# 3_-_19V_Buck.net
KiCad netlist of a schematic drawn in Altium Designer
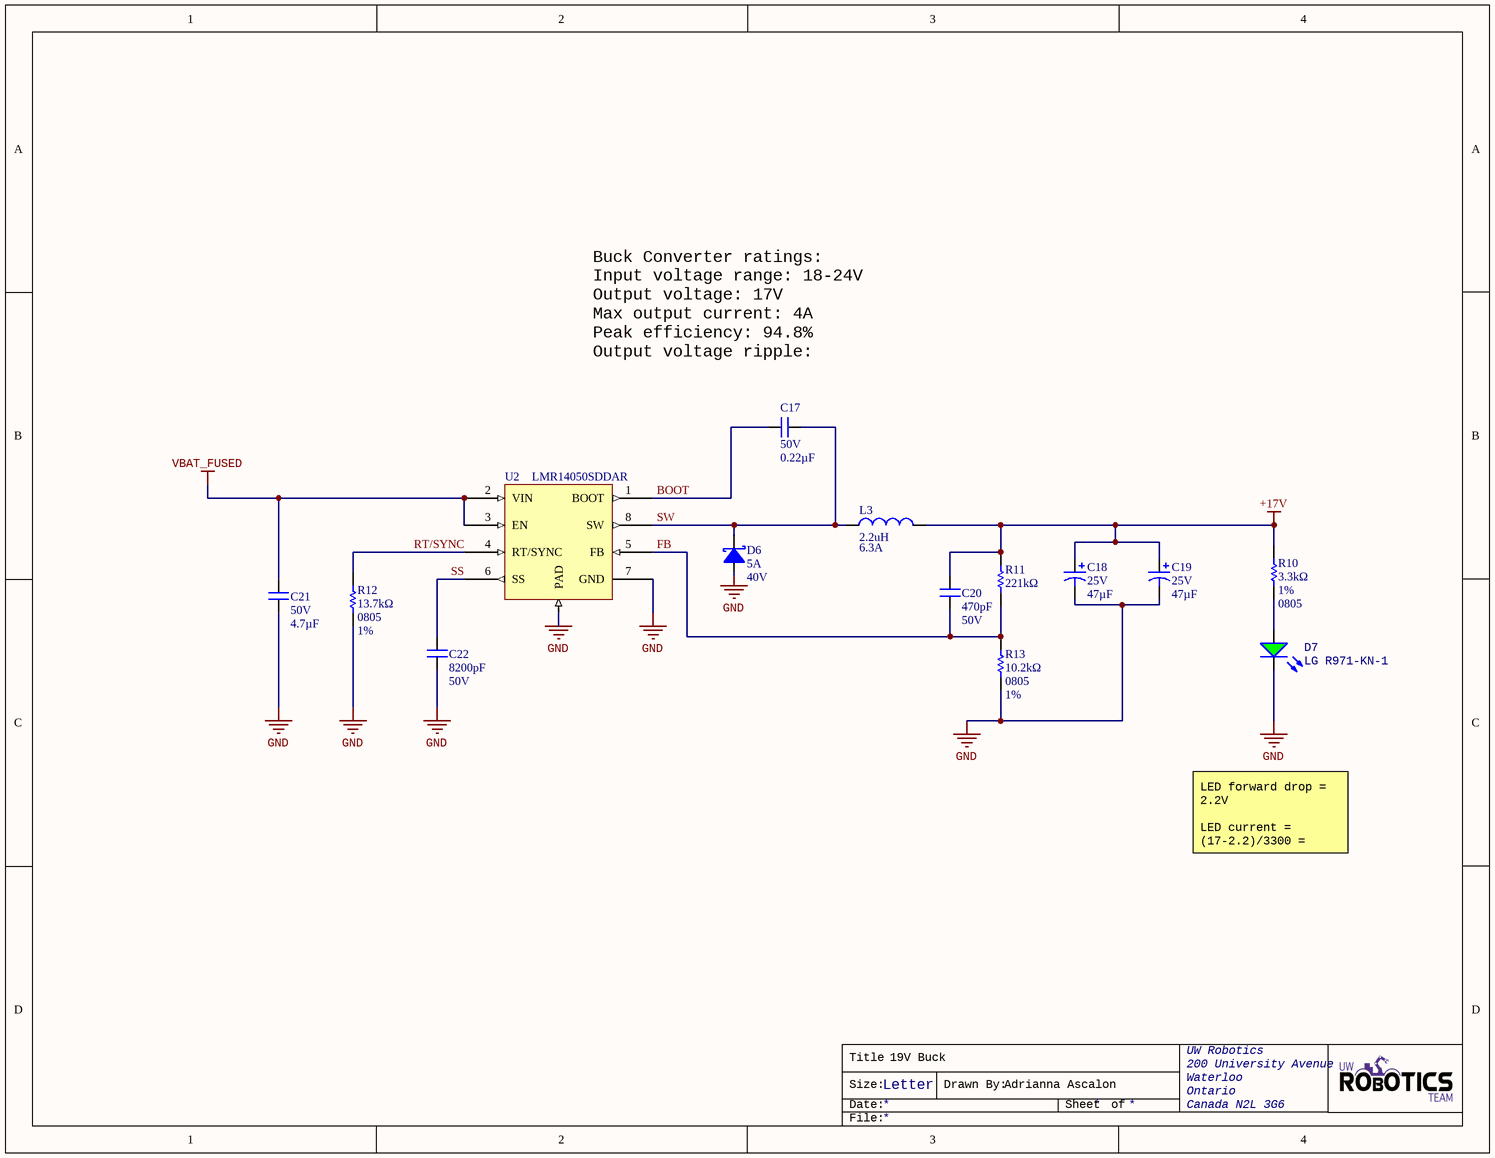
[diagram p0: 3 - 19V Buck.SchDoc]

(export (version "E")
  (design (tool "Eeschema 10.0.6"))
  (components
    (comp (ref "C17")
      (value "GRM21BR71H224MA01L")
      (footprint "CAP 0805_2012")
      (description "CAP CER 0.22UF 50V X7R 0805")
      (fields
        (field (name "TOLERANCE") "20%")
        (field (name "VOLTAGE RATING") "50V")
        (field (name "CAPACITANCE") "0.22µF")
      )
      (libsource (lib "UWRT_Schematic_Library_2020") (part "GRM21BR71H224MA01L"))
    )
    (comp (ref "C18")
      (value "47μF")
      (footprint "25SVPF47M")
      (description "CAP ALUM POLY 47UF 20% 25V SMD")
      (fields
        (field (name "TOLERANCE") "20%")
        (field (name "VOLTAGE") "25V")
        (field (name "CAPACITANCE") "47µF")
      )
      (libsource (lib "UWRT_Schematic_Library_2020") (part "25SVPF47M"))
    )
    (comp (ref "C19")
      (value "47μF")
      (footprint "25SVPF47M")
      (description "CAP ALUM POLY 47UF 20% 25V SMD")
      (fields
        (field (name "TOLERANCE") "20%")
        (field (name "VOLTAGE") "25V")
        (field (name "CAPACITANCE") "47µF")
      )
      (libsource (lib "UWRT_Schematic_Library_2020") (part "25SVPF47M"))
    )
    (comp (ref "C20")
      (value "470pF")
      (footprint "CAP 0805_2012")
      (description "CAP CER 470PF 50V X7R 0805")
      (fields (field (name "VOLTAGE RATING") "50V") (field (name "TOLERANCE") "5%"))
      (libsource (lib "UWRT_Schematic_Library_2020") (part "CAP_470pF_50V_0805"))
    )
    (comp (ref "C21")
      (value "GRM31CR71H475KA12L")
      (footprint "CAPC1206(3216)")
      (description "CAP CER 4.7UF 50V X7R 1206")
      (fields
        (field (name "TOLERANCE") "10%")
        (field (name "VOLTAGE") "50V")
        (field (name "VOLTAGE RATING") "50V")
        (field (name "CAPACITANCE") "4.7µF")
      )
      (libsource (lib "UWRT_Schematic_Library_2020") (part "GRM31CR71H475KA12L"))
    )
    (comp (ref "C22")
      (value "8200pF")
      (description "CAP CER 8200PF 50V X7R 0805")
      (fields (field (name "TOLERANCE") "10%") (field (name "VOLTAGE RATING") "50V"))
      (libsource (lib "UWRT_Schematic_Library_2020") (part "CAP_8200pF_50V_0805"))
    )
    (comp (ref "D6")
      (value "B540C-13-F")
      (footprint "DO214AB SMC")
      (description "Diode Schottky 40V 5A Surface Mount SMC")
      (fields (field (name "FORWARD CURRENT") "5A") (field (name "VOLTAGE") "40V"))
      (libsource (lib "UWRT_Schematic_Library_2020") (part "B540C-13-F"))
    )
    (comp (ref "D7")
      (value "LG R971-KN-1")
      (footprint "LED_0805_LINE")
      (description "LED GREEN DIFFUSED 0805 SMD")
      (libsource (lib "UWRT_Schematic_Library_2020") (part "DIO_LED_G"))
    )
    (comp (ref "L3")
      (value "SRN8040-2R2Y")
      (footprint "IND_BOURNS_SRN80")
      (description "FIXED IND 2.2UH 6.3A 13 MOHM SMD")
      (fields
        (field (name "TOLERANCE") "30%")
        (field (name "INDUCTANCE") "2.2uH")
        (field (name "MAX DC CURRENT") "6.3A")
      )
      (libsource (lib "UWRT_Schematic_Library_2020") (part "SRN8040-2R2Y"))
    )
    (comp (ref "R10")
      (value "3.3kΩ")
      (description "RES SMD 3.3K OHM 1% 1/8W 0805")
      (fields (field (name "TOLERANCE") "1%") (field (name "CASE CODE (IMPERIAL)") "0805"))
      (libsource (lib "UWRT_Schematic_Library_2020") (part "RES_3.3kΩ_0805"))
    )
    (comp (ref "R11")
      (value "221kΩ")
      (footprint "RESC2012X60N")
      (description "RES SMD 221K OHM 1% 1/8W 0805")
      (fields (field (name "TOLERANCE") "1%"))
      (libsource (lib "UWRT_Schematic_Library_2020") (part "RES_221kΩ_0805"))
    )
    (comp (ref "R12")
      (value "13.7kΩ")
      (footprint "RESC2012X60N")
      (description "RES SMD 13.7K OHM 1% 1/8W 0805")
      (fields (field (name "CASE CODE (IMPERIAL)") "0805") (field (name "TOLERANCE") "1%"))
      (libsource (lib "UWRT_Schematic_Library_2020") (part "RES_13.7kΩ_0805"))
    )
    (comp (ref "R13")
      (value "10.2kΩ")
      (footprint "RESC2012X60N")
      (description "RES SMD 10.2K OHM 1% 1/8W 0805")
      (fields (field (name "CASE CODE (IMPERIAL)") "0805") (field (name "TOLERANCE") "1%"))
      (libsource (lib "UWRT_Schematic_Library_2020") (part "RES_10.2kΩ_0805"))
    )
    (comp (ref "U2")
      (value "LMR14050SDDAR")
      (footprint "UWRT_Footprint_Library_2020:DDA8")
      (description "Buck, 40V, 5A  2.2MHz Step-Down Regulator with 40µA IQ 8-SO PowerPAD -40 to 125")
      (libsource (lib "UWRT_Schematic_Library_2020") (part "LMR14050SDDAR"))
    )
  )
  (nets
    (net (code "1") (name "+17V") (class "Default")
      (node (ref "C18") (pin "1") (pinfunction "1_1") (pintype "passive"))
      (node (ref "C19") (pin "1") (pinfunction "1_1") (pintype "passive"))
      (node (ref "C20") (pin "2") (pinfunction "2_2") (pintype "passive"))
      (node (ref "L3") (pin "2") (pinfunction "2_2") (pintype "passive"))
      (node (ref "R10") (pin "2") (pinfunction "2_2") (pintype "passive"))
      (node (ref "R11") (pin "2") (pinfunction "2_2") (pintype "passive"))
    )
    (net (code "2") (name "/BOOT") (class "Default")
      (node (ref "C17") (pin "2") (pinfunction "2_2") (pintype "passive"))
      (node (ref "U2") (pin "1") (pinfunction "BOOT_1") (pintype "output"))
    )
    (net (code "3") (name "/FB") (class "Default")
      (node (ref "C20") (pin "1") (pinfunction "1_1") (pintype "passive"))
      (node (ref "R11") (pin "1") (pinfunction "1_1") (pintype "passive"))
      (node (ref "R13") (pin "2") (pinfunction "2_2") (pintype "passive"))
      (node (ref "U2") (pin "5") (pinfunction "FB_5") (pintype "input"))
    )
    (net (code "4") (name "/RT{slash}SYNC") (class "Default")
      (node (ref "R12") (pin "2") (pinfunction "2_2") (pintype "passive"))
      (node (ref "U2") (pin "4") (pinfunction "RT/SYNC_4") (pintype "input"))
    )
    (net (code "5") (name "/SS") (class "Default")
      (node (ref "C22") (pin "2") (pinfunction "2_2") (pintype "passive"))
      (node (ref "U2") (pin "6") (pinfunction "SS_6") (pintype "output"))
    )
    (net (code "6") (name "/SW") (class "Default")
      (node (ref "C17") (pin "1") (pinfunction "1_1") (pintype "passive"))
      (node (ref "D6") (pin "2") (pinfunction "Cathode_2") (pintype "passive"))
      (node (ref "L3") (pin "1") (pinfunction "1_1") (pintype "passive"))
      (node (ref "U2") (pin "8") (pinfunction "SW_8") (pintype "output"))
    )
    (net (code "7") (name "GND") (class "Default")
      (node (ref "C18") (pin "2") (pinfunction "2_2") (pintype "passive"))
      (node (ref "C19") (pin "2") (pinfunction "2_2") (pintype "passive"))
      (node (ref "C21") (pin "2") (pinfunction "2_2") (pintype "passive"))
      (node (ref "C22") (pin "1") (pinfunction "1_1") (pintype "passive"))
      (node (ref "D6") (pin "1") (pinfunction "Anode_1") (pintype "passive"))
      (node (ref "D7") (pin "2") (pinfunction "K_2") (pintype "passive"))
      (node (ref "R12") (pin "1") (pinfunction "1_1") (pintype "passive"))
      (node (ref "R13") (pin "1") (pinfunction "1_1") (pintype "passive"))
      (node (ref "U2") (pin "7") (pinfunction "GND_7") (pintype "power_in"))
      (node (ref "U2") (pin "9") (pinfunction "PAD_9") (pintype "input"))
    )
    (net (code "8") (name "Net-(D7-A)") (class "Default")
      (node (ref "D7") (pin "1") (pinfunction "A_1") (pintype "passive"))
      (node (ref "R10") (pin "1") (pinfunction "1_1") (pintype "passive"))
    )
    (net (code "9") (name "VBAT_FUSED") (class "Default")
      (node (ref "C21") (pin "1") (pinfunction "1_1") (pintype "passive"))
      (node (ref "U2") (pin "2") (pinfunction "VIN_2") (pintype "input"))
      (node (ref "U2") (pin "3") (pinfunction "EN_3") (pintype "input"))
    )
  )
)
